# portal_parkir.net
KiCad netlist of a schematic drawn in EAGLE
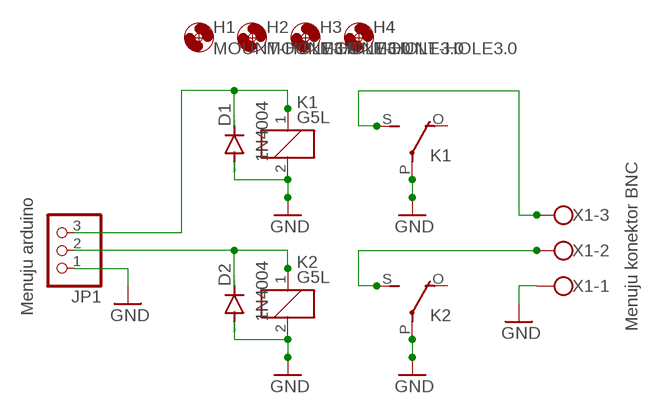
[diagram p0: schematic, sheet 1]

(export (version "E")
  (design (tool "Eeschema 10.0.6"))
  (components
    (comp (ref "D1")
      (value "1N4004")
      (footprint "eagle-import:DO41-10")
      (libsource (lib "eagle-import") (part "1N4004"))
    )
    (comp (ref "D2")
      (value "1N4004")
      (footprint "eagle-import:DO41-10")
      (libsource (lib "eagle-import") (part "1N4004"))
    )
    (comp (ref "H1")
      (value "MOUNT-HOLE3.0")
      (footprint "eagle-import:3,0")
      (libsource (lib "eagle-import") (part "MOUNT-HOLE3.0"))
    )
    (comp (ref "H2")
      (value "MOUNT-HOLE3.0")
      (footprint "eagle-import:3,0")
      (libsource (lib "eagle-import") (part "MOUNT-HOLE3.0"))
    )
    (comp (ref "H3")
      (value "MOUNT-HOLE3.0")
      (footprint "eagle-import:3,0")
      (libsource (lib "eagle-import") (part "MOUNT-HOLE3.0"))
    )
    (comp (ref "H4")
      (value "MOUNT-HOLE3.0")
      (footprint "eagle-import:3,0")
      (libsource (lib "eagle-import") (part "MOUNT-HOLE3.0"))
    )
    (comp (ref "JP1")
      (value "PINHD-1X3")
      (footprint "eagle-import:1X03")
      (libsource (lib "eagle-import") (part "PINHD-1X3"))
    )
    (comp (ref "K1")
      (value "G5L")
      (footprint "eagle-import:G5LE")
      (libsource (lib "eagle-import") (part "G5L"))
    )
    (comp (ref "K2")
      (value "G5L")
      (footprint "eagle-import:G5LE")
      (libsource (lib "eagle-import") (part "G5L"))
    )
    (comp (ref "X1")
      (value "W237-103")
      (footprint "eagle-import:W237-103")
      (fields (field (name "MPN") "237-103"))
      (libsource (lib "eagle-import") (part "W237-103"))
    )
  )
  (nets
    (net (code "1") (name "GND") (class "Default")
      (node (ref "D1") (pin "A") (pinfunction "A_A") (pintype "passive"))
      (node (ref "D2") (pin "A") (pinfunction "A_A") (pintype "passive"))
      (node (ref "JP1") (pin "1") (pinfunction "1_1") (pintype "passive"))
      (node (ref "K1") (pin "2") (pinfunction "2_2") (pintype "passive"))
      (node (ref "K1") (pin "P") (pinfunction "P_P") (pintype "passive"))
      (node (ref "K2") (pin "2") (pinfunction "2_2") (pintype "passive"))
      (node (ref "K2") (pin "P") (pinfunction "P_P") (pintype "passive"))
      (node (ref "X1") (pin "1") (pinfunction "KL_1") (pintype "passive"))
    )
    (net (code "2") (name "Net-(D1-PadC)") (class "Default")
      (node (ref "D1") (pin "C") (pinfunction "C_C") (pintype "passive"))
      (node (ref "JP1") (pin "3") (pinfunction "3_3") (pintype "passive"))
      (node (ref "K1") (pin "1") (pinfunction "1_1") (pintype "passive"))
    )
    (net (code "3") (name "Net-(D2-PadC)") (class "Default")
      (node (ref "D2") (pin "C") (pinfunction "C_C") (pintype "passive"))
      (node (ref "JP1") (pin "2") (pinfunction "2_2") (pintype "passive"))
      (node (ref "K2") (pin "1") (pinfunction "1_1") (pintype "passive"))
    )
    (net (code "4") (name "Net-(X1B-KL)") (class "Default")
      (node (ref "K2") (pin "S") (pinfunction "S_S") (pintype "passive"))
      (node (ref "X1") (pin "2") (pinfunction "KL_2") (pintype "passive"))
    )
    (net (code "5") (name "Net-(X1C-KL)") (class "Default")
      (node (ref "K1") (pin "S") (pinfunction "S_S") (pintype "passive"))
      (node (ref "X1") (pin "3") (pinfunction "KL_3") (pintype "passive"))
    )
    (net (code "6") (name "unconnected-(K1-PadO)") (class "Default")
      (node (ref "K1") (pin "O") (pinfunction "O_O") (pintype "passive"))
    )
    (net (code "7") (name "unconnected-(K2-PadO)") (class "Default")
      (node (ref "K2") (pin "O") (pinfunction "O_O") (pintype "passive"))
    )
  )
)
